# Soil_Module.net
KiCad netlist of a schematic drawn in EAGLE
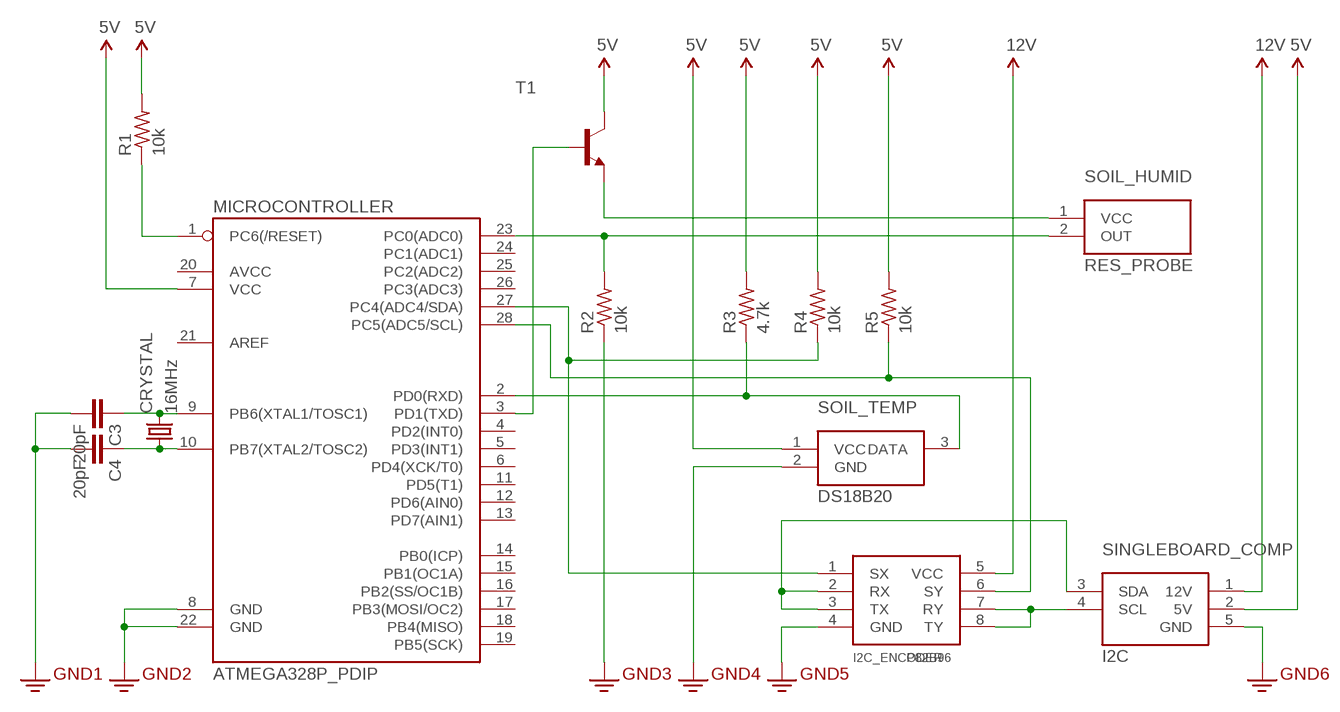
[diagram p0: schematic, sheet 1]

(export (version "E")
  (design (tool "Eeschema 10.0.6"))
  (components
    (comp (ref "C3")
      (value "20pF")
      (footprint "eagle-import:CAP-PTH-SMALL")
      (libsource (lib "eagle-import") (part "CAPPTH"))
    )
    (comp (ref "C4")
      (value "20pF")
      (footprint "eagle-import:CAP-PTH-SMALL")
      (libsource (lib "eagle-import") (part "CAPPTH"))
    )
    (comp (ref "CRYSTAL")
      (value "16MHz")
      (footprint "eagle-import:HC49US")
      (libsource (lib "eagle-import") (part "CRYSTALHC49US"))
    )
    (comp (ref "I2C_ENCODER")
      (value "P82B96")
      (footprint "eagle-import:DIP08")
      (libsource (lib "eagle-import") (part "P82B96"))
    )
    (comp (ref "MICROCONTROLLER")
      (value "ATMEGA328P_PDIP")
      (footprint "eagle-import:DIL28-3")
      (libsource (lib "eagle-import") (part "ATMEGA328P_PDIP"))
    )
    (comp (ref "R1")
      (value "10k")
      (footprint "eagle-import:0204_7")
      (libsource (lib "eagle-import") (part "R-US_0204/7"))
    )
    (comp (ref "R2")
      (value "10k")
      (footprint "eagle-import:0204_7")
      (libsource (lib "eagle-import") (part "R-US_0204/7"))
    )
    (comp (ref "R3")
      (value "4.7k")
      (footprint "eagle-import:0204_7")
      (libsource (lib "eagle-import") (part "R-US_0204/7"))
    )
    (comp (ref "R4")
      (value "10k")
      (footprint "eagle-import:0204_7")
      (libsource (lib "eagle-import") (part "R-US_0204/7"))
    )
    (comp (ref "R5")
      (value "10k")
      (footprint "eagle-import:0204_7")
      (libsource (lib "eagle-import") (part "R-US_0204/7"))
    )
    (comp (ref "SINGLEBOARD_COMP")
      (value "I2C")
      (footprint "eagle-import:I2C_TERM")
      (libsource (lib "eagle-import") (part "I2C"))
    )
    (comp (ref "SOIL_HUMID")
      (value "RES_PROBE")
      (footprint "eagle-import:SOIL_MOISTURE")
      (libsource (lib "eagle-import") (part "RES_PROBE"))
    )
    (comp (ref "SOIL_TEMP")
      (value "DS18B20")
      (footprint "eagle-import:SOIL_TEMP")
      (libsource (lib "eagle-import") (part "DS18B20"))
    )
    (comp (ref "T1")
      (value "2N2222A-NPN-TO18-EBC")
      (footprint "eagle-import:TO18")
      (libsource (lib "eagle-import") (part "-NPN-TO18-EBC2N2222A"))
    )
  )
  (nets
    (net (code "1") (name "5V") (class "Default")
      (node (ref "MICROCONTROLLER") (pin "7") (pinfunction "VCC_7") (pintype "bidirectional"))
      (node (ref "R1") (pin "2") (pinfunction "2_2") (pintype "passive"))
      (node (ref "R3") (pin "2") (pinfunction "2_2") (pintype "passive"))
      (node (ref "R4") (pin "2") (pinfunction "2_2") (pintype "passive"))
      (node (ref "R5") (pin "2") (pinfunction "2_2") (pintype "passive"))
      (node (ref "SINGLEBOARD_COMP") (pin "2") (pinfunction "5V_2") (pintype "bidirectional"))
      (node (ref "SOIL_TEMP") (pin "1") (pinfunction "VCC_1") (pintype "bidirectional"))
      (node (ref "T1") (pin "3") (pinfunction "C_3") (pintype "passive"))
    )
    (net (code "2") (name "12V") (class "Default")
      (node (ref "I2C_ENCODER") (pin "5") (pinfunction "VCC_5") (pintype "bidirectional"))
      (node (ref "SINGLEBOARD_COMP") (pin "1") (pinfunction "12V_1") (pintype "bidirectional"))
    )
    (net (code "3") (name "GND2") (class "Default")
      (node (ref "C3") (pin "2") (pinfunction "2_2") (pintype "passive"))
      (node (ref "C4") (pin "2") (pinfunction "2_2") (pintype "passive"))
      (node (ref "I2C_ENCODER") (pin "4") (pinfunction "GND_4") (pintype "bidirectional"))
      (node (ref "MICROCONTROLLER") (pin "22") (pinfunction "GND_22") (pintype "bidirectional"))
      (node (ref "MICROCONTROLLER") (pin "8") (pinfunction "GND_8") (pintype "bidirectional"))
      (node (ref "R2") (pin "1") (pinfunction "1_1") (pintype "passive"))
      (node (ref "SINGLEBOARD_COMP") (pin "5") (pinfunction "GND_5") (pintype "bidirectional"))
      (node (ref "SOIL_TEMP") (pin "2") (pinfunction "GND_2") (pintype "bidirectional"))
    )
    (net (code "4") (name "Net-(I2C_ENCODER-RX)") (class "Default")
      (node (ref "I2C_ENCODER") (pin "2") (pinfunction "RX_2") (pintype "bidirectional"))
      (node (ref "I2C_ENCODER") (pin "3") (pinfunction "TX_3") (pintype "bidirectional"))
      (node (ref "SINGLEBOARD_COMP") (pin "3") (pinfunction "SDA_3") (pintype "bidirectional"))
    )
    (net (code "5") (name "Net-(I2C_ENCODER-RY)") (class "Default")
      (node (ref "I2C_ENCODER") (pin "7") (pinfunction "RY_7") (pintype "bidirectional"))
      (node (ref "I2C_ENCODER") (pin "8") (pinfunction "TY_8") (pintype "bidirectional"))
      (node (ref "SINGLEBOARD_COMP") (pin "4") (pinfunction "SCL_4") (pintype "bidirectional"))
    )
    (net (code "6") (name "Net-(I2C_ENCODER-SX)") (class "Default")
      (node (ref "I2C_ENCODER") (pin "1") (pinfunction "SX_1") (pintype "bidirectional"))
      (node (ref "MICROCONTROLLER") (pin "27") (pinfunction "PC4(ADC4/SDA)_27") (pintype "bidirectional"))
      (node (ref "R4") (pin "1") (pinfunction "1_1") (pintype "passive"))
    )
    (net (code "7") (name "Net-(I2C_ENCODER-SY)") (class "Default")
      (node (ref "I2C_ENCODER") (pin "6") (pinfunction "SY_6") (pintype "bidirectional"))
      (node (ref "MICROCONTROLLER") (pin "28") (pinfunction "PC5(ADC5/SCL)_28") (pintype "bidirectional"))
      (node (ref "R5") (pin "1") (pinfunction "1_1") (pintype "passive"))
    )
    (net (code "8") (name "Net-(MICROCONTROLLER-PB6(XTAL1{slash}TOSC1))") (class "Default")
      (node (ref "C3") (pin "1") (pinfunction "1_1") (pintype "passive"))
      (node (ref "CRYSTAL") (pin "2") (pinfunction "2_2") (pintype "passive"))
      (node (ref "MICROCONTROLLER") (pin "9") (pinfunction "PB6(XTAL1/TOSC1)_9") (pintype "bidirectional"))
    )
    (net (code "9") (name "Net-(MICROCONTROLLER-PB7(XTAL2{slash}TOSC2))") (class "Default")
      (node (ref "C4") (pin "1") (pinfunction "1_1") (pintype "passive"))
      (node (ref "CRYSTAL") (pin "1") (pinfunction "1_1") (pintype "passive"))
      (node (ref "MICROCONTROLLER") (pin "10") (pinfunction "PB7(XTAL2/TOSC2)_10") (pintype "bidirectional"))
    )
    (net (code "10") (name "Net-(MICROCONTROLLER-PC0(ADC0))") (class "Default")
      (node (ref "MICROCONTROLLER") (pin "23") (pinfunction "PC0(ADC0)_23") (pintype "bidirectional"))
      (node (ref "R2") (pin "2") (pinfunction "2_2") (pintype "passive"))
      (node (ref "SOIL_HUMID") (pin "2") (pinfunction "OUT_2") (pintype "bidirectional"))
    )
    (net (code "11") (name "Net-(MICROCONTROLLER-PC6({slash}RESET))") (class "Default")
      (node (ref "MICROCONTROLLER") (pin "1") (pinfunction "PC6(/RESET)_1") (pintype "bidirectional"))
      (node (ref "R1") (pin "1") (pinfunction "1_1") (pintype "passive"))
    )
    (net (code "12") (name "Net-(MICROCONTROLLER-PD0(RXD))") (class "Default")
      (node (ref "MICROCONTROLLER") (pin "2") (pinfunction "PD0(RXD)_2") (pintype "bidirectional"))
      (node (ref "R3") (pin "1") (pinfunction "1_1") (pintype "passive"))
      (node (ref "SOIL_TEMP") (pin "3") (pinfunction "DATA_3") (pintype "bidirectional"))
    )
    (net (code "13") (name "Net-(MICROCONTROLLER-PD1(TXD))") (class "Default")
      (node (ref "MICROCONTROLLER") (pin "3") (pinfunction "PD1(TXD)_3") (pintype "bidirectional"))
      (node (ref "T1") (pin "2") (pinfunction "B_2") (pintype "passive"))
    )
    (net (code "14") (name "Net-(SOIL_HUMID-VCC)") (class "Default")
      (node (ref "SOIL_HUMID") (pin "1") (pinfunction "VCC_1") (pintype "bidirectional"))
      (node (ref "T1") (pin "1") (pinfunction "E_1") (pintype "passive"))
    )
    (net (code "15") (name "unconnected-(MICROCONTROLLER-AREF-Pad21)") (class "Default")
      (node (ref "MICROCONTROLLER") (pin "21") (pinfunction "AREF_21") (pintype "bidirectional"))
    )
    (net (code "16") (name "unconnected-(MICROCONTROLLER-AVCC-Pad20)") (class "Default")
      (node (ref "MICROCONTROLLER") (pin "20") (pinfunction "AVCC_20") (pintype "bidirectional"))
    )
    (net (code "17") (name "unconnected-(MICROCONTROLLER-PB0(ICP)-Pad14)") (class "Default")
      (node (ref "MICROCONTROLLER") (pin "14") (pinfunction "PB0(ICP)_14") (pintype "bidirectional"))
    )
    (net (code "18") (name "unconnected-(MICROCONTROLLER-PB1(OC1A)-Pad15)") (class "Default")
      (node (ref "MICROCONTROLLER") (pin "15") (pinfunction "PB1(OC1A)_15") (pintype "bidirectional"))
    )
    (net (code "19") (name "unconnected-(MICROCONTROLLER-PB2(SS{slash}OC1B)-Pad16)") (class "Default")
      (node (ref "MICROCONTROLLER") (pin "16") (pinfunction "PB2(SS/OC1B)_16") (pintype "bidirectional"))
    )
    (net (code "20") (name "unconnected-(MICROCONTROLLER-PB3(MOSI{slash}OC2)-Pad17)") (class "Default")
      (node (ref "MICROCONTROLLER") (pin "17") (pinfunction "PB3(MOSI/OC2)_17") (pintype "bidirectional"))
    )
    (net (code "21") (name "unconnected-(MICROCONTROLLER-PB4(MISO)-Pad18)") (class "Default")
      (node (ref "MICROCONTROLLER") (pin "18") (pinfunction "PB4(MISO)_18") (pintype "bidirectional"))
    )
    (net (code "22") (name "unconnected-(MICROCONTROLLER-PB5(SCK)-Pad19)") (class "Default")
      (node (ref "MICROCONTROLLER") (pin "19") (pinfunction "PB5(SCK)_19") (pintype "bidirectional"))
    )
    (net (code "23") (name "unconnected-(MICROCONTROLLER-PC1(ADC1)-Pad24)") (class "Default")
      (node (ref "MICROCONTROLLER") (pin "24") (pinfunction "PC1(ADC1)_24") (pintype "bidirectional"))
    )
    (net (code "24") (name "unconnected-(MICROCONTROLLER-PC2(ADC2)-Pad25)") (class "Default")
      (node (ref "MICROCONTROLLER") (pin "25") (pinfunction "PC2(ADC2)_25") (pintype "bidirectional"))
    )
    (net (code "25") (name "unconnected-(MICROCONTROLLER-PC3(ADC3)-Pad26)") (class "Default")
      (node (ref "MICROCONTROLLER") (pin "26") (pinfunction "PC3(ADC3)_26") (pintype "bidirectional"))
    )
    (net (code "26") (name "unconnected-(MICROCONTROLLER-PD2(INT0)-Pad4)") (class "Default")
      (node (ref "MICROCONTROLLER") (pin "4") (pinfunction "PD2(INT0)_4") (pintype "bidirectional"))
    )
    (net (code "27") (name "unconnected-(MICROCONTROLLER-PD3(INT1)-Pad5)") (class "Default")
      (node (ref "MICROCONTROLLER") (pin "5") (pinfunction "PD3(INT1)_5") (pintype "bidirectional"))
    )
    (net (code "28") (name "unconnected-(MICROCONTROLLER-PD4(XCK{slash}T0)-Pad6)") (class "Default")
      (node (ref "MICROCONTROLLER") (pin "6") (pinfunction "PD4(XCK/T0)_6") (pintype "bidirectional"))
    )
    (net (code "29") (name "unconnected-(MICROCONTROLLER-PD5(T1)-Pad11)") (class "Default")
      (node (ref "MICROCONTROLLER") (pin "11") (pinfunction "PD5(T1)_11") (pintype "bidirectional"))
    )
    (net (code "30") (name "unconnected-(MICROCONTROLLER-PD6(AIN0)-Pad12)") (class "Default")
      (node (ref "MICROCONTROLLER") (pin "12") (pinfunction "PD6(AIN0)_12") (pintype "bidirectional"))
    )
    (net (code "31") (name "unconnected-(MICROCONTROLLER-PD7(AIN1)-Pad13)") (class "Default")
      (node (ref "MICROCONTROLLER") (pin "13") (pinfunction "PD7(AIN1)_13") (pintype "bidirectional"))
    )
  )
)
